# Nano_Screw_Terminal_Adapter.net
KiCad netlist of a schematic drawn in Altium Designer
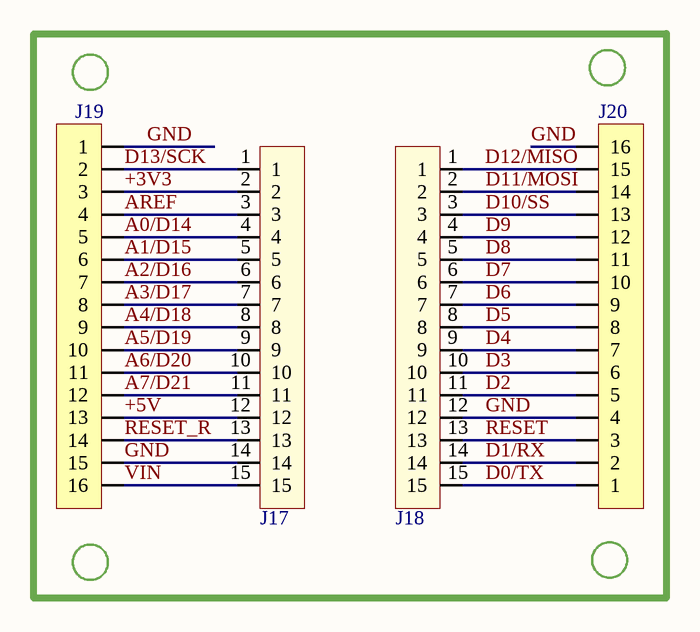
[diagram p0: Nano Screw Terminal Adapter.SchDoc]

(export (version "E")
  (design (tool "Eeschema 10.0.6"))
  (components
    (comp (ref "J17")
      (value "HLE-115-02-F-DV")
      (footprint "HLE-115-02-F-DV-Footprint-1")
      (description "Board Connector, 30 Contact(s), 2 Row(s), Female, Straight, Surface Mount Terminal, Socket GPinto")
      (fields (field (name "MANUFACTURER") "Samtec"))
      (libsource (lib "") (part "HLE-115-02-F-DV-Symbol-1_1"))
    )
    (comp (ref "J18")
      (value "HLE-115-02-F-DV")
      (footprint "HLE-115-02-F-DV-Footprint-1")
      (description "Board Connector, 30 Contact(s), 2 Row(s), Female, Straight, Surface Mount Terminal, Socket GPinto")
      (fields (field (name "MANUFACTURER") "Samtec"))
      (libsource (lib "Clean") (part "HLE-115-02-F-DV-Symbol-1"))
    )
    (comp (ref "J19")
      (value "22TW-277")
      (footprint "MK125002GO")
      (description "CONN MORS.CS 16v p3,5 10A aLING.VER BLACK")
      (fields (field (name "MANUFACTURER") "4U CON"))
      (libsource (lib "Clean") (part "22TW-277"))
    )
    (comp (ref "J20")
      (value "22TW-277")
      (footprint "MK125002GO")
      (description "CONN MORS.CS 16v p3,5 10A aLING.VER BLACK")
      (fields (field (name "MANUFACTURER") "4U CON"))
      (libsource (lib "") (part "22TW-277_1"))
    )
  )
  (nets
    (net (code "1") (name "/+3V3") (class "Default")
      (node (ref "J17") (pin "2") (pinfunction "2_2") (pintype "passive"))
      (node (ref "J19") (pin "3") (pinfunction "3_3") (pintype "passive"))
    )
    (net (code "2") (name "/+5V") (class "Default")
      (node (ref "J17") (pin "12") (pinfunction "12_12") (pintype "passive"))
      (node (ref "J19") (pin "13") (pinfunction "13_13") (pintype "passive"))
    )
    (net (code "3") (name "/A0{slash}D14") (class "Default")
      (node (ref "J17") (pin "4") (pinfunction "4_4") (pintype "passive"))
      (node (ref "J19") (pin "5") (pinfunction "5_5") (pintype "passive"))
    )
    (net (code "4") (name "/A1{slash}D15") (class "Default")
      (node (ref "J17") (pin "5") (pinfunction "5_5") (pintype "passive"))
      (node (ref "J19") (pin "6") (pinfunction "6_6") (pintype "passive"))
    )
    (net (code "5") (name "/A2{slash}D16") (class "Default")
      (node (ref "J17") (pin "6") (pinfunction "6_6") (pintype "passive"))
      (node (ref "J19") (pin "7") (pinfunction "7_7") (pintype "passive"))
    )
    (net (code "6") (name "/A3{slash}D17") (class "Default")
      (node (ref "J17") (pin "7") (pinfunction "7_7") (pintype "passive"))
      (node (ref "J19") (pin "8") (pinfunction "8_8") (pintype "passive"))
    )
    (net (code "7") (name "/A4{slash}D18") (class "Default")
      (node (ref "J17") (pin "8") (pinfunction "8_8") (pintype "passive"))
      (node (ref "J19") (pin "9") (pinfunction "9_9") (pintype "passive"))
    )
    (net (code "8") (name "/A5{slash}D19") (class "Default")
      (node (ref "J17") (pin "9") (pinfunction "9_9") (pintype "passive"))
      (node (ref "J19") (pin "10") (pinfunction "10_10") (pintype "passive"))
    )
    (net (code "9") (name "/A6{slash}D20") (class "Default")
      (node (ref "J17") (pin "10") (pinfunction "10_10") (pintype "passive"))
      (node (ref "J19") (pin "11") (pinfunction "11_11") (pintype "passive"))
    )
    (net (code "10") (name "/A7{slash}D21") (class "Default")
      (node (ref "J17") (pin "11") (pinfunction "11_11") (pintype "passive"))
      (node (ref "J19") (pin "12") (pinfunction "12_12") (pintype "passive"))
    )
    (net (code "11") (name "/AREF") (class "Default")
      (node (ref "J17") (pin "3") (pinfunction "3_3") (pintype "passive"))
      (node (ref "J19") (pin "4") (pinfunction "4_4") (pintype "passive"))
    )
    (net (code "12") (name "/D0{slash}TX") (class "Default")
      (node (ref "J18") (pin "15") (pinfunction "15_15") (pintype "passive"))
      (node (ref "J20") (pin "1") (pinfunction "1_1") (pintype "passive"))
    )
    (net (code "13") (name "/D1{slash}RX") (class "Default")
      (node (ref "J18") (pin "14") (pinfunction "14_14") (pintype "passive"))
      (node (ref "J20") (pin "2") (pinfunction "2_2") (pintype "passive"))
    )
    (net (code "14") (name "/D2") (class "Default")
      (node (ref "J18") (pin "11") (pinfunction "11_11") (pintype "passive"))
      (node (ref "J20") (pin "5") (pinfunction "5_5") (pintype "passive"))
    )
    (net (code "15") (name "/D3") (class "Default")
      (node (ref "J18") (pin "10") (pinfunction "10_10") (pintype "passive"))
      (node (ref "J20") (pin "6") (pinfunction "6_6") (pintype "passive"))
    )
    (net (code "16") (name "/D4") (class "Default")
      (node (ref "J18") (pin "9") (pinfunction "9_9") (pintype "passive"))
      (node (ref "J20") (pin "7") (pinfunction "7_7") (pintype "passive"))
    )
    (net (code "17") (name "/D5") (class "Default")
      (node (ref "J18") (pin "8") (pinfunction "8_8") (pintype "passive"))
      (node (ref "J20") (pin "8") (pinfunction "8_8") (pintype "passive"))
    )
    (net (code "18") (name "/D6") (class "Default")
      (node (ref "J18") (pin "7") (pinfunction "7_7") (pintype "passive"))
      (node (ref "J20") (pin "9") (pinfunction "9_9") (pintype "passive"))
    )
    (net (code "19") (name "/D7") (class "Default")
      (node (ref "J18") (pin "6") (pinfunction "6_6") (pintype "passive"))
      (node (ref "J20") (pin "10") (pinfunction "10_10") (pintype "passive"))
    )
    (net (code "20") (name "/D8") (class "Default")
      (node (ref "J18") (pin "5") (pinfunction "5_5") (pintype "passive"))
      (node (ref "J20") (pin "11") (pinfunction "11_11") (pintype "passive"))
    )
    (net (code "21") (name "/D9") (class "Default")
      (node (ref "J18") (pin "4") (pinfunction "4_4") (pintype "passive"))
      (node (ref "J20") (pin "12") (pinfunction "12_12") (pintype "passive"))
    )
    (net (code "22") (name "/D10{slash}SS") (class "Default")
      (node (ref "J18") (pin "3") (pinfunction "3_3") (pintype "passive"))
      (node (ref "J20") (pin "13") (pinfunction "13_13") (pintype "passive"))
    )
    (net (code "23") (name "/D11{slash}MOSI") (class "Default")
      (node (ref "J18") (pin "2") (pinfunction "2_2") (pintype "passive"))
      (node (ref "J20") (pin "14") (pinfunction "14_14") (pintype "passive"))
    )
    (net (code "24") (name "/D12{slash}MISO") (class "Default")
      (node (ref "J18") (pin "1") (pinfunction "1_1") (pintype "passive"))
      (node (ref "J20") (pin "15") (pinfunction "15_15") (pintype "passive"))
    )
    (net (code "25") (name "/D13{slash}SCK") (class "Default")
      (node (ref "J17") (pin "1") (pinfunction "1_1") (pintype "passive"))
      (node (ref "J19") (pin "2") (pinfunction "2_2") (pintype "passive"))
    )
    (net (code "26") (name "/GND") (class "Default")
      (node (ref "J17") (pin "14") (pinfunction "14_14") (pintype "passive"))
      (node (ref "J18") (pin "12") (pinfunction "12_12") (pintype "passive"))
      (node (ref "J19") (pin "1") (pinfunction "1_1") (pintype "passive"))
      (node (ref "J19") (pin "15") (pinfunction "15_15") (pintype "passive"))
      (node (ref "J20") (pin "16") (pinfunction "16_16") (pintype "passive"))
      (node (ref "J20") (pin "4") (pinfunction "4_4") (pintype "passive"))
    )
    (net (code "27") (name "/RESET") (class "Default")
      (node (ref "J18") (pin "13") (pinfunction "13_13") (pintype "passive"))
      (node (ref "J20") (pin "3") (pinfunction "3_3") (pintype "passive"))
    )
    (net (code "28") (name "/RESET_R") (class "Default")
      (node (ref "J17") (pin "13") (pinfunction "13_13") (pintype "passive"))
      (node (ref "J19") (pin "14") (pinfunction "14_14") (pintype "passive"))
    )
    (net (code "29") (name "/VIN") (class "Default")
      (node (ref "J17") (pin "15") (pinfunction "15_15") (pintype "passive"))
      (node (ref "J19") (pin "16") (pinfunction "16_16") (pintype "passive"))
    )
  )
)
